# Schematic.net
KiCad netlist of a schematic drawn in Altium Designer
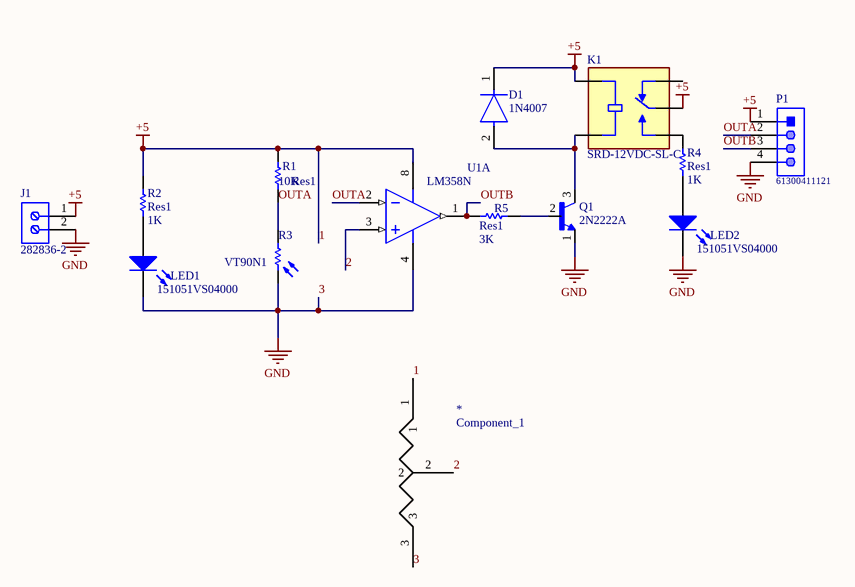
[diagram p0: Schematic.SchDoc]

(export (version "E")
  (design (tool "Eeschema 10.0.6"))
  (components
    (comp (ref "*")
      (value "Component_1")
      (footprint "PCBComponent_1")
      (libsource (lib "Integrated_Library1") (part "Component_1"))
    )
    (comp (ref "D1")
      (value "1N4007")
      (footprint "FP-1N4007-MFG")
      (description "Rectifier diode 1000 V 1 A DO-41, ,")
      (fields
        (field (name "MANUFACTURER") "Diotec")
        (field (name "OCTOPART") "https://octopart.com/1n4007-diotec-4040411")
      )
      (libsource (lib "Altium Content Vault") (part "d7152d700b627762746794eb795d46e"))
    )
    (comp (ref "J1")
      (value "282836-2")
      (footprint "TECO-282836-2_V")
      (description "Female Header, Pitch 5 mm, 1 x 2 Position, Height 10 mm, Tail Length 3.5 mm, Rohs, Bulk")
      (fields (field (name "VOLTAGE") "300V") (field (name "MANUFACTURER") "TE Connectivity"))
      (libsource (lib "Altium Content Vault") (part "CN-1P-F-TB2"))
    )
    (comp (ref "K1")
      (value "SRD-12VDC-SL-C")
      (footprint "SRD-12VDC-SL-C:RELAY_SRD-12VDC-SL-C")
      (description "General Purpose Non Latching 12VDC SPDT Through Hole Relays RoHS")
      (fields (field (name "MF") "{'manufacturer': u'Songle Relay'}"))
      (libsource (lib "*") (part "SRD-12VDC-SL-C"))
    )
    (comp (ref "LED1")
      (value "151051VS04000")
      (footprint "Type 5mm")
      (description "THT LED round mono-color color lens, WL-TMRW, Bright Green")
      (fields (field (name "MANUFACTURER") "Wuerth Elektronik"))
      (libsource (lib "Altium Content Vault") (part "WE-LED_K1A2-2"))
    )
    (comp (ref "LED2")
      (value "151051VS04000")
      (footprint "Type 5mm")
      (description "THT LED round mono-color color lens, WL-TMRW, Bright Green")
      (fields (field (name "MANUFACTURER") "Wuerth Elektronik"))
      (libsource (lib "Altium Content Vault") (part "WE-LED_K1A2-2"))
    )
    (comp (ref "P1")
      (value "61300411121")
      (footprint "61300411121")
      (description "THT Vertical Pin Header WR-PHD, Pitch 2.54 mm, Single Row, 4 pins")
      (fields (field (name "MANUFACTURER") "Wurth Elektronik") (field (name "PUBLISHER") "WurthElektronik"))
      (libsource (lib "Altium Content Vault") (part "WE-CN-1P-M-R4"))
    )
    (comp (ref "Q1")
      (value "2N2222A")
      (footprint "2N2222A:TO127P584H533-3")
      (description "2N2222A 50 V 800 mA NPN Silicon Switching Transistor - TO-18 (TO-206AA)")
      (fields (field (name "MF") "{'manufacturer': u'Diotec Semiconductor'}"))
      (libsource (lib "*") (part "2N2222A"))
    )
    (comp (ref "R1")
      (value "Res1")
      (footprint "AXIAL-0.3")
      (description "Resistor")
      (fields (field (name "ALTIUM_VALUE") "10K") (field (name "PUBLISHER") "Altium Limited"))
      (libsource (lib "Miscellaneous Devices") (part "Res1"))
    )
    (comp (ref "R2")
      (value "Res1")
      (footprint "AXIAL-0.3")
      (description "Resistor")
      (fields (field (name "ALTIUM_VALUE") "1K") (field (name "PUBLISHER") "Altium Limited"))
      (libsource (lib "Miscellaneous Devices") (part "Res1"))
    )
    (comp (ref "R3")
      (value "VT90N1")
      (footprint "EXCE-VT90N1")
      (description "Photoconductive Resistor, 200 kOhm, 100 V, 80 mW, -40 to 75 degC, 2-Pin THD, RoHS")
      (fields (field (name "MANUFACTURER") "Excelitas Technology"))
      (libsource (lib "Altium Content Vault") (part "PHOTO-RES-2"))
    )
    (comp (ref "R4")
      (value "Res1")
      (footprint "AXIAL-0.3")
      (description "Resistor")
      (fields (field (name "ALTIUM_VALUE") "1K") (field (name "PUBLISHER") "Altium Limited"))
      (libsource (lib "Miscellaneous Devices") (part "Res1"))
    )
    (comp (ref "R5")
      (value "Res1")
      (footprint "AXIAL-0.3")
      (description "Resistor")
      (fields (field (name "ALTIUM_VALUE") "3K") (field (name "PUBLISHER") "Altium Limited"))
      (libsource (lib "Miscellaneous Devices") (part "Res1"))
    )
    (comp (ref "U1")
      (value "LM358N")
      (footprint "ONSC-PDIP-8-626-05_M")
      (description "Single Supply Dual Operational Amplifier, 3 to 32 V, 0 to 70 degC, 8-Pin PDIP, Tube")
      (fields (field (name "MANUFACTURER") "On Semiconductor"))
      (libsource (lib "Altium Content Vault") (part "ONSC-LM358_NCV2904-8"))
    )
  )
  (nets
    (net (code "1") (name "+5") (class "Default")
      (node (ref "*") (pin "1") (pinfunction "1_1") (pintype "passive"))
      (node (ref "D1") (pin "1") (pinfunction "C_1") (pintype "passive"))
      (node (ref "J1") (pin "1") (pinfunction "1_1") (pintype "passive"))
      (node (ref "K1") (pin "COIL1") (pinfunction "COIL1_COIL1") (pintype "passive"))
      (node (ref "K1") (pin "COM") (pinfunction "COM_COM") (pintype "passive"))
      (node (ref "P1") (pin "1") (pinfunction "1_1") (pintype "passive"))
      (node (ref "R1") (pin "2") (pinfunction "2_2") (pintype "passive"))
      (node (ref "R2") (pin "2") (pinfunction "2_2") (pintype "passive"))
      (node (ref "U1") (pin "8") (pinfunction "VCC_8") (pintype "power_in"))
    )
    (net (code "2") (name "/2") (class "Default")
      (node (ref "*") (pin "2") (pinfunction "2_2") (pintype "passive"))
      (node (ref "U1") (pin "3") (pinfunction "INA+_3") (pintype "input"))
    )
    (net (code "3") (name "/OUTA") (class "Default")
      (node (ref "P1") (pin "2") (pinfunction "2_2") (pintype "passive"))
      (node (ref "R1") (pin "1") (pinfunction "1_1") (pintype "passive"))
      (node (ref "R3") (pin "1") (pinfunction "1_1") (pintype "passive"))
      (node (ref "U1") (pin "2") (pinfunction "INA-_2") (pintype "input"))
    )
    (net (code "4") (name "/OUTB") (class "Default")
      (node (ref "P1") (pin "3") (pinfunction "3_3") (pintype "passive"))
      (node (ref "R5") (pin "1") (pinfunction "1_1") (pintype "passive"))
      (node (ref "U1") (pin "1") (pinfunction "OUTA_1") (pintype "output"))
    )
    (net (code "5") (name "GND") (class "Default")
      (node (ref "*") (pin "3") (pinfunction "3_3") (pintype "passive"))
      (node (ref "J1") (pin "2") (pinfunction "2_2") (pintype "passive"))
      (node (ref "LED1") (pin "1") (pinfunction "K_1") (pintype "passive"))
      (node (ref "LED2") (pin "1") (pinfunction "K_1") (pintype "passive"))
      (node (ref "P1") (pin "4") (pinfunction "4_4") (pintype "passive"))
      (node (ref "Q1") (pin "1") (pinfunction "E_1") (pintype "passive"))
      (node (ref "R3") (pin "2") (pinfunction "2_2") (pintype "passive"))
      (node (ref "U1") (pin "4") (pinfunction "VEE/GND_4") (pintype "power_in"))
    )
    (net (code "6") (name "Net-(D1-A)") (class "Default")
      (node (ref "D1") (pin "2") (pinfunction "A_2") (pintype "passive"))
      (node (ref "K1") (pin "COIL2") (pinfunction "COIL2_COIL2") (pintype "passive"))
      (node (ref "Q1") (pin "3") (pinfunction "C_3") (pintype "passive"))
    )
    (net (code "7") (name "Net-(K1-PadNO)") (class "Default")
      (node (ref "K1") (pin "NO") (pinfunction "NO_NO") (pintype "passive"))
      (node (ref "R4") (pin "2") (pinfunction "2_2") (pintype "passive"))
    )
    (net (code "8") (name "Net-(LED1-A)") (class "Default")
      (node (ref "LED1") (pin "2") (pinfunction "A_2") (pintype "passive"))
      (node (ref "R2") (pin "1") (pinfunction "1_1") (pintype "passive"))
    )
    (net (code "9") (name "Net-(LED2-A)") (class "Default")
      (node (ref "LED2") (pin "2") (pinfunction "A_2") (pintype "passive"))
      (node (ref "R4") (pin "1") (pinfunction "1_1") (pintype "passive"))
    )
    (net (code "10") (name "Net-(Q1-B)") (class "Default")
      (node (ref "Q1") (pin "2") (pinfunction "B_2") (pintype "passive"))
      (node (ref "R5") (pin "2") (pinfunction "2_2") (pintype "passive"))
    )
    (net (code "11") (name "unconnected-(K1-PadNC)") (class "Default")
      (node (ref "K1") (pin "NC") (pinfunction "NC_NC") (pintype "passive"))
    )
  )
)
